# 3.net
KiCad netlist of a schematic drawn in EasyEDA Pro
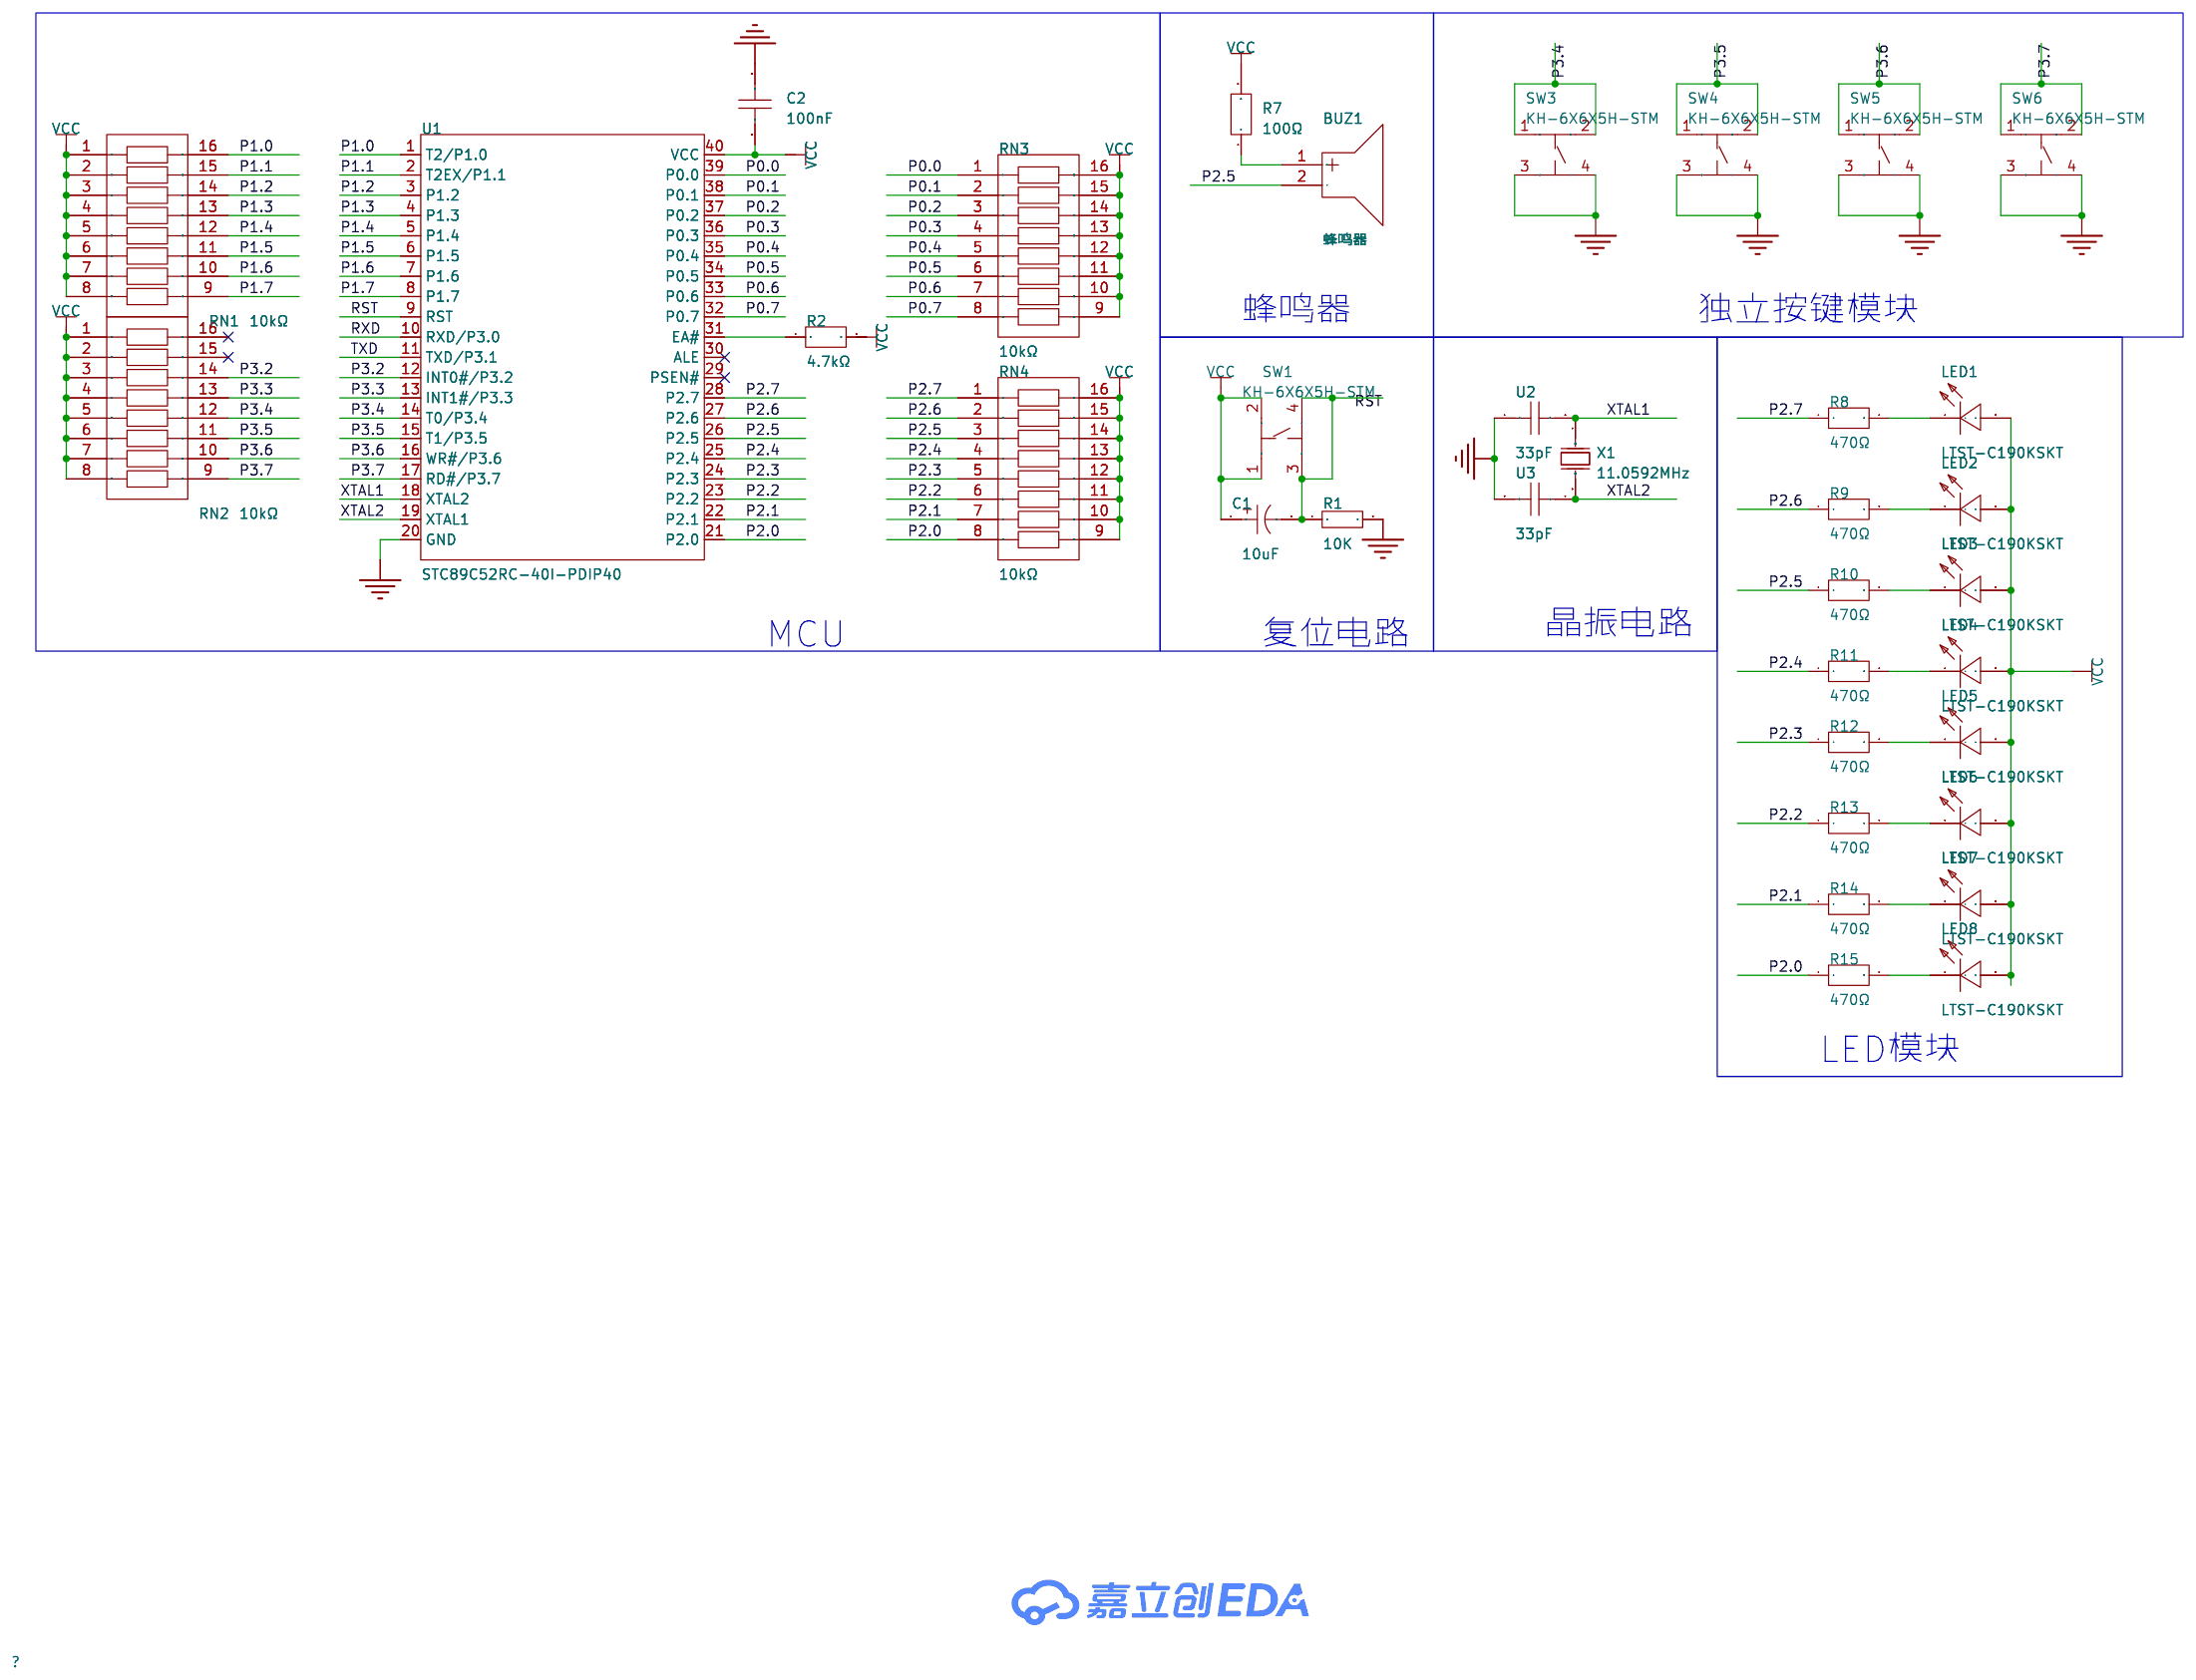
[diagram p0: schematic sheet]

(export (version "E")
  (design (tool "Eeschema 10.0.6"))
  (components
    (comp (ref "BUZ1")
      (value "蜂鸣器")
      (footprint "easyedapro:BUZ-TH_BD9.0-P5.00-D0.6-FD")
      (libsource (lib "easyedapro") (part "蜂鸣器"))
    )
    (comp (ref "C1")
      (value "10uF")
      (footprint "easyedapro:CAP-TH_BD10.0-P5.00-D0.6-FD_1")
      (description "容值:10uF;精度:±20%;额定电压:450V;纹波电流:200mA@100kHz;等效串联电阻(ESR):9Ω@100kHz;")
      (fields (field (name "Manufacturer Part") "CV100MPA16B") (field (name "Manufacturer") "TWBOR(伯鸿)"))
      (libsource (lib "easyedapro") (part "CV100MPA16B"))
    )
    (comp (ref "C2")
      (value "100nF")
      (footprint "easyedapro:C0603")
      (description "容值:100nF;精度:±10%;额定电压:25V;温度系数:X7R;")
      (fields
        (field (name "Manufacturer Part") "0603X7R104K250NT")
        (field (name "Manufacturer") "AIDE(爱迪电容)")
      )
      (libsource (lib "easyedapro") (part "0603X7R104K250NT"))
    )
    (comp (ref "LED1")
      (value "LTST-C190KSKT")
      (footprint "easyedapro:LED0603-RD")
      (fields (field (name "Manufacturer") "LITEON(光宝)"))
      (libsource (lib "easyedapro") (part "LTST-C190KSKT"))
    )
    (comp (ref "LED2")
      (value "LTST-C190KSKT")
      (footprint "easyedapro:LED0603-RD")
      (fields (field (name "Manufacturer") "LITEON(光宝)"))
      (libsource (lib "easyedapro") (part "LTST-C190KSKT"))
    )
    (comp (ref "LED3")
      (value "LTST-C190KSKT")
      (footprint "easyedapro:LED0603-RD")
      (fields (field (name "Manufacturer") "LITEON(光宝)"))
      (libsource (lib "easyedapro") (part "LTST-C190KSKT"))
    )
    (comp (ref "LED4")
      (value "LTST-C190KSKT")
      (footprint "easyedapro:LED0603-RD")
      (fields (field (name "Manufacturer") "LITEON(光宝)"))
      (libsource (lib "easyedapro") (part "LTST-C190KSKT"))
    )
    (comp (ref "LED5")
      (value "LTST-C190KSKT")
      (footprint "easyedapro:LED0603-RD")
      (fields (field (name "Manufacturer") "LITEON(光宝)"))
      (libsource (lib "easyedapro") (part "LTST-C190KSKT"))
    )
    (comp (ref "LED6")
      (value "LTST-C190KSKT")
      (footprint "easyedapro:LED0603-RD")
      (fields (field (name "Manufacturer") "LITEON(光宝)"))
      (libsource (lib "easyedapro") (part "LTST-C190KSKT"))
    )
    (comp (ref "LED7")
      (value "LTST-C190KSKT")
      (footprint "easyedapro:LED0603-RD")
      (fields (field (name "Manufacturer") "LITEON(光宝)"))
      (libsource (lib "easyedapro") (part "LTST-C190KSKT"))
    )
    (comp (ref "LED8")
      (value "LTST-C190KSKT")
      (footprint "easyedapro:LED0603-RD")
      (fields (field (name "Manufacturer") "LITEON(光宝)"))
      (libsource (lib "easyedapro") (part "LTST-C190KSKT"))
    )
    (comp (ref "R1") (value "10K") (footprint "easyedapro:R0603") (libsource (lib "easyedapro") (part "电阻")))
    (comp (ref "R2")
      (value "4.7kΩ")
      (footprint "easyedapro:R0805")
      (description "电阻类型:厚膜电阻;阻值:4.7kΩ;精度:±1%;功率:125mW;工作电压:-;温度系数:±100ppm/°C;")
      (fields
        (field (name "Manufacturer Part") "ERJ-U06F4701V")
        (field (name "Manufacturer") "PANASONIC(松下)")
      )
      (libsource (lib "easyedapro") (part "ERJ-U06F4701V"))
    )
    (comp (ref "R7")
      (value "100Ω")
      (footprint "easyedapro:R1206")
      (description "电阻类型:-;阻值:100Ω;精度:±5%;功率:250mW;工作电压:200V;")
      (fields
        (field (name "Manufacturer Part") "CQ06W4J0101T5E")
        (field (name "Manufacturer") "UNI-ROYAL(厚声)")
      )
      (libsource (lib "easyedapro") (part "CQ06W4J0101T5E"))
    )
    (comp (ref "R8")
      (value "470Ω")
      (footprint "easyedapro:R0402")
      (description "电阻类型:厚膜电阻;阻值:470Ω;精度:±1%;功率:62.5mW;工作电压:50V;温度系数:±100ppm/°C;")
      (fields (field (name "Manufacturer Part") "FRC0402F4700TS") (field (name "Manufacturer") "FOJAN(富捷)"))
      (libsource (lib "easyedapro") (part "FRC0402F4700TS"))
    )
    (comp (ref "R9")
      (value "470Ω")
      (footprint "easyedapro:R0402")
      (description "电阻类型:厚膜电阻;阻值:470Ω;精度:±1%;功率:62.5mW;工作电压:50V;温度系数:±100ppm/°C;")
      (fields (field (name "Manufacturer Part") "FRC0402F4700TS") (field (name "Manufacturer") "FOJAN(富捷)"))
      (libsource (lib "easyedapro") (part "FRC0402F4700TS"))
    )
    (comp (ref "R10")
      (value "470Ω")
      (footprint "easyedapro:R0402")
      (description "电阻类型:厚膜电阻;阻值:470Ω;精度:±1%;功率:62.5mW;工作电压:50V;温度系数:±100ppm/°C;")
      (fields (field (name "Manufacturer Part") "FRC0402F4700TS") (field (name "Manufacturer") "FOJAN(富捷)"))
      (libsource (lib "easyedapro") (part "FRC0402F4700TS"))
    )
    (comp (ref "R11")
      (value "470Ω")
      (footprint "easyedapro:R0402")
      (description "电阻类型:厚膜电阻;阻值:470Ω;精度:±1%;功率:62.5mW;工作电压:50V;温度系数:±100ppm/°C;")
      (fields (field (name "Manufacturer Part") "FRC0402F4700TS") (field (name "Manufacturer") "FOJAN(富捷)"))
      (libsource (lib "easyedapro") (part "FRC0402F4700TS"))
    )
    (comp (ref "R12")
      (value "470Ω")
      (footprint "easyedapro:R0402")
      (description "电阻类型:厚膜电阻;阻值:470Ω;精度:±1%;功率:62.5mW;工作电压:50V;温度系数:±100ppm/°C;")
      (fields (field (name "Manufacturer Part") "FRC0402F4700TS") (field (name "Manufacturer") "FOJAN(富捷)"))
      (libsource (lib "easyedapro") (part "FRC0402F4700TS"))
    )
    (comp (ref "R13")
      (value "470Ω")
      (footprint "easyedapro:R0402")
      (description "电阻类型:厚膜电阻;阻值:470Ω;精度:±1%;功率:62.5mW;工作电压:50V;温度系数:±100ppm/°C;")
      (fields (field (name "Manufacturer Part") "FRC0402F4700TS") (field (name "Manufacturer") "FOJAN(富捷)"))
      (libsource (lib "easyedapro") (part "FRC0402F4700TS"))
    )
    (comp (ref "R14")
      (value "470Ω")
      (footprint "easyedapro:R0402")
      (description "电阻类型:厚膜电阻;阻值:470Ω;精度:±1%;功率:62.5mW;工作电压:50V;温度系数:±100ppm/°C;")
      (fields (field (name "Manufacturer Part") "FRC0402F4700TS") (field (name "Manufacturer") "FOJAN(富捷)"))
      (libsource (lib "easyedapro") (part "FRC0402F4700TS"))
    )
    (comp (ref "R15")
      (value "470Ω")
      (footprint "easyedapro:R0402")
      (description "电阻类型:厚膜电阻;阻值:470Ω;精度:±1%;功率:62.5mW;工作电压:50V;温度系数:±100ppm/°C;")
      (fields (field (name "Manufacturer Part") "FRC0402F4700TS") (field (name "Manufacturer") "FOJAN(富捷)"))
      (libsource (lib "easyedapro") (part "FRC0402F4700TS"))
    )
    (comp (ref "RN1")
      (value "10kΩ")
      (footprint "easyedapro:DIP-16_L22.0-W6.7-P2.54-LS7.6-BL")
      (description "电阻器数:8;阻值:10kΩ;精度:±2%;单个元件功率:250mW;温度系数:±100ppm/°C;")
      (fields (field (name "Manufacturer Part") "4116R-1-103LF") (field (name "Manufacturer") "BOURNS"))
      (libsource (lib "easyedapro") (part "4116R-1-103LF"))
    )
    (comp (ref "RN2")
      (value "10kΩ")
      (footprint "easyedapro:DIP-16_L22.0-W6.7-P2.54-LS7.6-BL")
      (description "电阻器数:8;阻值:10kΩ;精度:±2%;单个元件功率:250mW;温度系数:±100ppm/°C;")
      (fields (field (name "Manufacturer Part") "4116R-1-103LF") (field (name "Manufacturer") "BOURNS"))
      (libsource (lib "easyedapro") (part "4116R-1-103LF"))
    )
    (comp (ref "RN3")
      (value "10kΩ")
      (footprint "easyedapro:DIP-16_L22.0-W6.7-P2.54-LS7.6-BL")
      (description "电阻器数:8;阻值:10kΩ;精度:±2%;单个元件功率:250mW;温度系数:±100ppm/°C;")
      (fields (field (name "Manufacturer Part") "4116R-1-103LF") (field (name "Manufacturer") "BOURNS"))
      (libsource (lib "easyedapro") (part "4116R-1-103LF"))
    )
    (comp (ref "RN4")
      (value "10kΩ")
      (footprint "easyedapro:DIP-16_L22.0-W6.7-P2.54-LS7.6-BL")
      (description "电阻器数:8;阻值:10kΩ;精度:±2%;单个元件功率:250mW;温度系数:±100ppm/°C;")
      (fields (field (name "Manufacturer Part") "4116R-1-103LF") (field (name "Manufacturer") "BOURNS"))
      (libsource (lib "easyedapro") (part "4116R-1-103LF"))
    )
    (comp (ref "SW1")
      (value "KH-6X6X5H-STM")
      (footprint "easyedapro:SW-SMD_4P-L6.0-W6.0-P4.50-LS9.0_H5.0")
      (description "电路结构:单刀单掷;按钮形状:圆形按钮;安装方式:立贴;开关长度:6mm;开关宽度:6mm;开关高度:5mm;带支架:不带;触点电流:50mA;额定电压(DC):12V;机械寿命:8万次;")
      (fields (field (name "Manufacturer") "kinghelm(金航标)"))
      (libsource (lib "easyedapro") (part "KH-6X6X5H-STM"))
    )
    (comp (ref "SW3")
      (value "KH-6X6X5H-STM")
      (footprint "easyedapro:SW-SMD_4P-L6.0-W6.0-P4.50-LS9.0_H5.0")
      (description "电路结构:单刀单掷;按钮形状:圆形按钮;安装方式:立贴;开关长度:6mm;开关宽度:6mm;开关高度:5mm;带支架:不带;触点电流:50mA;额定电压(DC):12V;机械寿命:8万次;")
      (fields (field (name "Manufacturer") "kinghelm(金航标)"))
      (libsource (lib "easyedapro") (part "KH-6X6X5H-STM"))
    )
    (comp (ref "SW4")
      (value "KH-6X6X5H-STM")
      (footprint "easyedapro:SW-SMD_4P-L6.0-W6.0-P4.50-LS9.0_H5.0")
      (description "电路结构:单刀单掷;按钮形状:圆形按钮;安装方式:立贴;开关长度:6mm;开关宽度:6mm;开关高度:5mm;带支架:不带;触点电流:50mA;额定电压(DC):12V;机械寿命:8万次;")
      (fields (field (name "Manufacturer") "kinghelm(金航标)"))
      (libsource (lib "easyedapro") (part "KH-6X6X5H-STM"))
    )
    (comp (ref "SW5")
      (value "KH-6X6X5H-STM")
      (footprint "easyedapro:SW-SMD_4P-L6.0-W6.0-P4.50-LS9.0_H5.0")
      (description "电路结构:单刀单掷;按钮形状:圆形按钮;安装方式:立贴;开关长度:6mm;开关宽度:6mm;开关高度:5mm;带支架:不带;触点电流:50mA;额定电压(DC):12V;机械寿命:8万次;")
      (fields (field (name "Manufacturer") "kinghelm(金航标)"))
      (libsource (lib "easyedapro") (part "KH-6X6X5H-STM"))
    )
    (comp (ref "SW6")
      (value "KH-6X6X5H-STM")
      (footprint "easyedapro:SW-SMD_4P-L6.0-W6.0-P4.50-LS9.0_H5.0")
      (description "电路结构:单刀单掷;按钮形状:圆形按钮;安装方式:立贴;开关长度:6mm;开关宽度:6mm;开关高度:5mm;带支架:不带;触点电流:50mA;额定电压(DC):12V;机械寿命:8万次;")
      (fields (field (name "Manufacturer") "kinghelm(金航标)"))
      (libsource (lib "easyedapro") (part "KH-6X6X5H-STM"))
    )
    (comp (ref "U1")
      (value "STC89C52RC-40I-PDIP40")
      (footprint "easyedapro:DIP-40_L52.0-W13.7-P2.54-LS15.2-BL")
      (description "CPU内核:51系列;应用领域:-;")
      (fields (field (name "Manufacturer") "STC"))
      (libsource (lib "easyedapro") (part "STC89C52RC-40I"))
    )
    (comp (ref "U2")
      (value "33pF")
      (footprint "easyedapro:C0603")
      (description "容值:33pF;精度:±1%;额定电压:50V;温度系数:-;")
      (fields
        (field (name "Manufacturer Part") "GRM1885C1H330FA01D")
        (field (name "Manufacturer") "muRata(村田)")
      )
      (libsource (lib "easyedapro") (part "GRM1885C1H330FA01D"))
    )
    (comp (ref "U3")
      (value "33pF")
      (footprint "easyedapro:C0603")
      (description "容值:33pF;精度:±1%;额定电压:50V;温度系数:-;")
      (fields
        (field (name "Manufacturer Part") "GRM1885C1H330FA01D")
        (field (name "Manufacturer") "muRata(村田)")
      )
      (libsource (lib "easyedapro") (part "GRM1885C1H330FA01D"))
    )
    (comp (ref "X1")
      (value "11.0592MHz")
      (footprint "easyedapro:HC-49US_L11.5-W4.5-P4.88")
      (description "晶振类型:直插晶振;频率:11.0592MHz;常温频差:±20ppm;负载电容:20pF;频率稳定度:±30ppm;")
      (fields
        (field (name "Manufacturer Part") "X49SD110592MSD2SC")
        (field (name "Manufacturer") "YXC(扬兴晶振)")
      )
      (libsource (lib "easyedapro") (part "X49SD110592MSD2SC"))
    )
  )
  (nets
    (net (code "1") (name "/P0.0") (class "Default")
      (node (ref "RN3") (pin "1") (pinfunction "1_1") (pintype "unspecified"))
      (node (ref "U1") (pin "39") (pinfunction "P0.0_39") (pintype "unspecified"))
    )
    (net (code "2") (name "/P0.1") (class "Default")
      (node (ref "RN3") (pin "2") (pinfunction "2_2") (pintype "unspecified"))
      (node (ref "U1") (pin "38") (pinfunction "P0.1_38") (pintype "unspecified"))
    )
    (net (code "3") (name "/P0.2") (class "Default")
      (node (ref "RN3") (pin "3") (pinfunction "3_3") (pintype "unspecified"))
      (node (ref "U1") (pin "37") (pinfunction "P0.2_37") (pintype "unspecified"))
    )
    (net (code "4") (name "/P0.3") (class "Default")
      (node (ref "RN3") (pin "4") (pinfunction "4_4") (pintype "unspecified"))
      (node (ref "U1") (pin "36") (pinfunction "P0.3_36") (pintype "unspecified"))
    )
    (net (code "5") (name "/P0.4") (class "Default")
      (node (ref "RN3") (pin "5") (pinfunction "5_5") (pintype "unspecified"))
      (node (ref "U1") (pin "35") (pinfunction "P0.4_35") (pintype "unspecified"))
    )
    (net (code "6") (name "/P0.5") (class "Default")
      (node (ref "RN3") (pin "6") (pinfunction "6_6") (pintype "unspecified"))
      (node (ref "U1") (pin "34") (pinfunction "P0.5_34") (pintype "unspecified"))
    )
    (net (code "7") (name "/P0.6") (class "Default")
      (node (ref "RN3") (pin "7") (pinfunction "7_7") (pintype "unspecified"))
      (node (ref "U1") (pin "33") (pinfunction "P0.6_33") (pintype "unspecified"))
    )
    (net (code "8") (name "/P0.7") (class "Default")
      (node (ref "RN3") (pin "8") (pinfunction "8_8") (pintype "unspecified"))
      (node (ref "U1") (pin "32") (pinfunction "P0.7_32") (pintype "unspecified"))
    )
    (net (code "9") (name "/P1.0") (class "Default")
      (node (ref "RN1") (pin "16") (pinfunction "16_16") (pintype "unspecified"))
      (node (ref "U1") (pin "1") (pinfunction "T2/P1.0_1") (pintype "unspecified"))
    )
    (net (code "10") (name "/P1.1") (class "Default")
      (node (ref "RN1") (pin "15") (pinfunction "15_15") (pintype "unspecified"))
      (node (ref "U1") (pin "2") (pinfunction "T2EX/P1.1_2") (pintype "unspecified"))
    )
    (net (code "11") (name "/P1.2") (class "Default")
      (node (ref "RN1") (pin "14") (pinfunction "14_14") (pintype "unspecified"))
      (node (ref "U1") (pin "3") (pinfunction "P1.2_3") (pintype "unspecified"))
    )
    (net (code "12") (name "/P1.3") (class "Default")
      (node (ref "RN1") (pin "13") (pinfunction "13_13") (pintype "unspecified"))
      (node (ref "U1") (pin "4") (pinfunction "P1.3_4") (pintype "unspecified"))
    )
    (net (code "13") (name "/P1.4") (class "Default")
      (node (ref "RN1") (pin "12") (pinfunction "12_12") (pintype "unspecified"))
      (node (ref "U1") (pin "5") (pinfunction "P1.4_5") (pintype "unspecified"))
    )
    (net (code "14") (name "/P1.5") (class "Default")
      (node (ref "RN1") (pin "11") (pinfunction "11_11") (pintype "unspecified"))
      (node (ref "U1") (pin "6") (pinfunction "P1.5_6") (pintype "unspecified"))
    )
    (net (code "15") (name "/P1.6") (class "Default")
      (node (ref "RN1") (pin "10") (pinfunction "10_10") (pintype "unspecified"))
      (node (ref "U1") (pin "7") (pinfunction "P1.6_7") (pintype "unspecified"))
    )
    (net (code "16") (name "/P1.7") (class "Default")
      (node (ref "RN1") (pin "9") (pinfunction "9_9") (pintype "unspecified"))
      (node (ref "U1") (pin "8") (pinfunction "P1.7_8") (pintype "unspecified"))
    )
    (net (code "17") (name "/P2.0") (class "Default")
      (node (ref "R15") (pin "1") (pinfunction "1_1") (pintype "unspecified"))
      (node (ref "RN4") (pin "8") (pinfunction "8_8") (pintype "unspecified"))
      (node (ref "U1") (pin "21") (pinfunction "P2.0_21") (pintype "unspecified"))
    )
    (net (code "18") (name "/P2.1") (class "Default")
      (node (ref "R14") (pin "1") (pinfunction "1_1") (pintype "unspecified"))
      (node (ref "RN4") (pin "7") (pinfunction "7_7") (pintype "unspecified"))
      (node (ref "U1") (pin "22") (pinfunction "P2.1_22") (pintype "unspecified"))
    )
    (net (code "19") (name "/P2.2") (class "Default")
      (node (ref "R13") (pin "1") (pinfunction "1_1") (pintype "unspecified"))
      (node (ref "RN4") (pin "6") (pinfunction "6_6") (pintype "unspecified"))
      (node (ref "U1") (pin "23") (pinfunction "P2.2_23") (pintype "unspecified"))
    )
    (net (code "20") (name "/P2.3") (class "Default")
      (node (ref "R12") (pin "1") (pinfunction "1_1") (pintype "unspecified"))
      (node (ref "RN4") (pin "5") (pinfunction "5_5") (pintype "unspecified"))
      (node (ref "U1") (pin "24") (pinfunction "P2.3_24") (pintype "unspecified"))
    )
    (net (code "21") (name "/P2.4") (class "Default")
      (node (ref "R11") (pin "1") (pinfunction "1_1") (pintype "unspecified"))
      (node (ref "RN4") (pin "4") (pinfunction "4_4") (pintype "unspecified"))
      (node (ref "U1") (pin "25") (pinfunction "P2.4_25") (pintype "unspecified"))
    )
    (net (code "22") (name "/P2.5") (class "Default")
      (node (ref "BUZ1") (pin "2") (pinfunction "-_2") (pintype "unspecified"))
      (node (ref "R10") (pin "1") (pinfunction "1_1") (pintype "unspecified"))
      (node (ref "RN4") (pin "3") (pinfunction "3_3") (pintype "unspecified"))
      (node (ref "U1") (pin "26") (pinfunction "P2.5_26") (pintype "unspecified"))
    )
    (net (code "23") (name "/P2.6") (class "Default")
      (node (ref "R9") (pin "1") (pinfunction "1_1") (pintype "unspecified"))
      (node (ref "RN4") (pin "2") (pinfunction "2_2") (pintype "unspecified"))
      (node (ref "U1") (pin "27") (pinfunction "P2.6_27") (pintype "unspecified"))
    )
    (net (code "24") (name "/P2.7") (class "Default")
      (node (ref "R8") (pin "1") (pinfunction "1_1") (pintype "unspecified"))
      (node (ref "RN4") (pin "1") (pinfunction "1_1") (pintype "unspecified"))
      (node (ref "U1") (pin "28") (pinfunction "P2.7_28") (pintype "unspecified"))
    )
    (net (code "25") (name "/P3.2") (class "Default")
      (node (ref "RN2") (pin "14") (pinfunction "14_14") (pintype "unspecified"))
      (node (ref "U1") (pin "12") (pinfunction "INT0#/P3.2_12") (pintype "unspecified"))
    )
    (net (code "26") (name "/P3.3") (class "Default")
      (node (ref "RN2") (pin "13") (pinfunction "13_13") (pintype "unspecified"))
      (node (ref "U1") (pin "13") (pinfunction "INT1#/P3.3_13") (pintype "unspecified"))
    )
    (net (code "27") (name "/P3.4") (class "Default")
      (node (ref "RN2") (pin "12") (pinfunction "12_12") (pintype "unspecified"))
      (node (ref "SW3") (pin "1") (pinfunction "1_1") (pintype "unspecified"))
      (node (ref "SW3") (pin "2") (pinfunction "2_2") (pintype "unspecified"))
      (node (ref "U1") (pin "14") (pinfunction "T0/P3.4_14") (pintype "unspecified"))
    )
    (net (code "28") (name "/P3.5") (class "Default")
      (node (ref "RN2") (pin "11") (pinfunction "11_11") (pintype "unspecified"))
      (node (ref "SW4") (pin "1") (pinfunction "1_1") (pintype "unspecified"))
      (node (ref "SW4") (pin "2") (pinfunction "2_2") (pintype "unspecified"))
      (node (ref "U1") (pin "15") (pinfunction "T1/P3.5_15") (pintype "unspecified"))
    )
    (net (code "29") (name "/P3.6") (class "Default")
      (node (ref "RN2") (pin "10") (pinfunction "10_10") (pintype "unspecified"))
      (node (ref "SW5") (pin "1") (pinfunction "1_1") (pintype "unspecified"))
      (node (ref "SW5") (pin "2") (pinfunction "2_2") (pintype "unspecified"))
      (node (ref "U1") (pin "16") (pinfunction "WR#/P3.6_16") (pintype "unspecified"))
    )
    (net (code "30") (name "/P3.7") (class "Default")
      (node (ref "RN2") (pin "9") (pinfunction "9_9") (pintype "unspecified"))
      (node (ref "SW6") (pin "1") (pinfunction "1_1") (pintype "unspecified"))
      (node (ref "SW6") (pin "2") (pinfunction "2_2") (pintype "unspecified"))
      (node (ref "U1") (pin "17") (pinfunction "RD#/P3.7_17") (pintype "unspecified"))
    )
    (net (code "31") (name "/RST") (class "Default")
      (node (ref "C1") (pin "2") (pinfunction "2_2") (pintype "input"))
      (node (ref "R1") (pin "1") (pinfunction "1_1") (pintype "input"))
      (node (ref "SW1") (pin "3") (pinfunction "3_3") (pintype "unspecified"))
      (node (ref "SW1") (pin "4") (pinfunction "4_4") (pintype "unspecified"))
      (node (ref "U1") (pin "9") (pinfunction "RST_9") (pintype "unspecified"))
    )
    (net (code "32") (name "/RXD") (class "Default")
      (node (ref "U1") (pin "10") (pinfunction "RXD/P3.0_10") (pintype "unspecified"))
    )
    (net (code "33") (name "/TXD") (class "Default")
      (node (ref "U1") (pin "11") (pinfunction "TXD/P3.1_11") (pintype "unspecified"))
    )
    (net (code "34") (name "/XTAL1") (class "Default")
      (node (ref "U1") (pin "18") (pinfunction "XTAL2_18") (pintype "unspecified"))
      (node (ref "U2") (pin "2") (pinfunction "2_2") (pintype "unspecified"))
      (node (ref "X1") (pin "1") (pinfunction "OSC1_1") (pintype "input"))
    )
    (net (code "35") (name "/XTAL2") (class "Default")
      (node (ref "U1") (pin "19") (pinfunction "XTAL1_19") (pintype "unspecified"))
      (node (ref "U3") (pin "1") (pinfunction "1_1") (pintype "unspecified"))
      (node (ref "X1") (pin "2") (pinfunction "OSC2_2") (pintype "input"))
    )
    (net (code "36") (name "GND") (class "Default")
      (node (ref "C2") (pin "2") (pinfunction "2_2") (pintype "unspecified"))
      (node (ref "R1") (pin "2") (pinfunction "2_2") (pintype "input"))
      (node (ref "SW3") (pin "3") (pinfunction "3_3") (pintype "unspecified"))
      (node (ref "SW3") (pin "4") (pinfunction "4_4") (pintype "unspecified"))
      (node (ref "SW4") (pin "3") (pinfunction "3_3") (pintype "unspecified"))
      (node (ref "SW4") (pin "4") (pinfunction "4_4") (pintype "unspecified"))
      (node (ref "SW5") (pin "3") (pinfunction "3_3") (pintype "unspecified"))
      (node (ref "SW5") (pin "4") (pinfunction "4_4") (pintype "unspecified"))
      (node (ref "SW6") (pin "3") (pinfunction "3_3") (pintype "unspecified"))
      (node (ref "SW6") (pin "4") (pinfunction "4_4") (pintype "unspecified"))
      (node (ref "U1") (pin "20") (pinfunction "GND_20") (pintype "unspecified"))
      (node (ref "U2") (pin "1") (pinfunction "1_1") (pintype "unspecified"))
      (node (ref "U3") (pin "2") (pinfunction "2_2") (pintype "unspecified"))
    )
    (net (code "37") (name "Net-(BUZ1-+)") (class "Default")
      (node (ref "BUZ1") (pin "1") (pinfunction "+_1") (pintype "unspecified"))
      (node (ref "R7") (pin "1") (pinfunction "1_1") (pintype "unspecified"))
    )
    (net (code "38") (name "Net-(LED1--)") (class "Default")
      (node (ref "LED1") (pin "1") (pinfunction "-_1") (pintype "unspecified"))
      (node (ref "R8") (pin "2") (pinfunction "2_2") (pintype "unspecified"))
    )
    (net (code "39") (name "Net-(LED2--)") (class "Default")
      (node (ref "LED2") (pin "1") (pinfunction "-_1") (pintype "unspecified"))
      (node (ref "R9") (pin "2") (pinfunction "2_2") (pintype "unspecified"))
    )
    (net (code "40") (name "Net-(LED3--)") (class "Default")
      (node (ref "LED3") (pin "1") (pinfunction "-_1") (pintype "unspecified"))
      (node (ref "R10") (pin "2") (pinfunction "2_2") (pintype "unspecified"))
    )
    (net (code "41") (name "Net-(LED4--)") (class "Default")
      (node (ref "LED4") (pin "1") (pinfunction "-_1") (pintype "unspecified"))
      (node (ref "R11") (pin "2") (pinfunction "2_2") (pintype "unspecified"))
    )
    (net (code "42") (name "Net-(LED5--)") (class "Default")
      (node (ref "LED5") (pin "1") (pinfunction "-_1") (pintype "unspecified"))
      (node (ref "R12") (pin "2") (pinfunction "2_2") (pintype "unspecified"))
    )
    (net (code "43") (name "Net-(LED6--)") (class "Default")
      (node (ref "LED6") (pin "1") (pinfunction "-_1") (pintype "unspecified"))
      (node (ref "R13") (pin "2") (pinfunction "2_2") (pintype "unspecified"))
    )
    (net (code "44") (name "Net-(LED7--)") (class "Default")
      (node (ref "LED7") (pin "1") (pinfunction "-_1") (pintype "unspecified"))
      (node (ref "R14") (pin "2") (pinfunction "2_2") (pintype "unspecified"))
    )
    (net (code "45") (name "Net-(LED8--)") (class "Default")
      (node (ref "LED8") (pin "1") (pinfunction "-_1") (pintype "unspecified"))
      (node (ref "R15") (pin "2") (pinfunction "2_2") (pintype "unspecified"))
    )
    (net (code "46") (name "Net-(U1-EA#)") (class "Default")
      (node (ref "R2") (pin "1") (pinfunction "1_1") (pintype "unspecified"))
      (node (ref "U1") (pin "31") (pinfunction "EA#_31") (pintype "unspecified"))
    )
    (net (code "47") (name "VCC") (class "Default")
      (node (ref "C1") (pin "1") (pinfunction "1_1") (pintype "input"))
      (node (ref "C2") (pin "1") (pinfunction "1_1") (pintype "unspecified"))
      (node (ref "LED1") (pin "2") (pinfunction "+_2") (pintype "unspecified"))
      (node (ref "LED2") (pin "2") (pinfunction "+_2") (pintype "unspecified"))
      (node (ref "LED3") (pin "2") (pinfunction "+_2") (pintype "unspecified"))
      (node (ref "LED4") (pin "2") (pinfunction "+_2") (pintype "unspecified"))
      (node (ref "LED5") (pin "2") (pinfunction "+_2") (pintype "unspecified"))
      (node (ref "LED6") (pin "2") (pinfunction "+_2") (pintype "unspecified"))
      (node (ref "LED7") (pin "2") (pinfunction "+_2") (pintype "unspecified"))
      (node (ref "LED8") (pin "2") (pinfunction "+_2") (pintype "unspecified"))
      (node (ref "R2") (pin "2") (pinfunction "2_2") (pintype "unspecified"))
      (node (ref "R7") (pin "2") (pinfunction "2_2") (pintype "unspecified"))
      (node (ref "RN1") (pin "1") (pinfunction "1_1") (pintype "unspecified"))
      (node (ref "RN1") (pin "2") (pinfunction "2_2") (pintype "unspecified"))
      (node (ref "RN1") (pin "3") (pinfunction "3_3") (pintype "unspecified"))
      (node (ref "RN1") (pin "4") (pinfunction "4_4") (pintype "unspecified"))
      (node (ref "RN1") (pin "5") (pinfunction "5_5") (pintype "unspecified"))
      (node (ref "RN1") (pin "6") (pinfunction "6_6") (pintype "unspecified"))
      (node (ref "RN1") (pin "7") (pinfunction "7_7") (pintype "unspecified"))
      (node (ref "RN1") (pin "8") (pinfunction "8_8") (pintype "unspecified"))
      (node (ref "RN2") (pin "1") (pinfunction "1_1") (pintype "unspecified"))
      (node (ref "RN2") (pin "2") (pinfunction "2_2") (pintype "unspecified"))
      (node (ref "RN2") (pin "3") (pinfunction "3_3") (pintype "unspecified"))
      (node (ref "RN2") (pin "4") (pinfunction "4_4") (pintype "unspecified"))
      (node (ref "RN2") (pin "5") (pinfunction "5_5") (pintype "unspecified"))
      (node (ref "RN2") (pin "6") (pinfunction "6_6") (pintype "unspecified"))
      (node (ref "RN2") (pin "7") (pinfunction "7_7") (pintype "unspecified"))
      (node (ref "RN2") (pin "8") (pinfunction "8_8") (pintype "unspecified"))
      (node (ref "RN3") (pin "10") (pinfunction "10_10") (pintype "unspecified"))
      (node (ref "RN3") (pin "11") (pinfunction "11_11") (pintype "unspecified"))
      (node (ref "RN3") (pin "12") (pinfunction "12_12") (pintype "unspecified"))
      (node (ref "RN3") (pin "13") (pinfunction "13_13") (pintype "unspecified"))
      (node (ref "RN3") (pin "14") (pinfunction "14_14") (pintype "unspecified"))
      (node (ref "RN3") (pin "15") (pinfunction "15_15") (pintype "unspecified"))
      (node (ref "RN3") (pin "16") (pinfunction "16_16") (pintype "unspecified"))
      (node (ref "RN3") (pin "9") (pinfunction "9_9") (pintype "unspecified"))
      (node (ref "RN4") (pin "10") (pinfunction "10_10") (pintype "unspecified"))
      (node (ref "RN4") (pin "11") (pinfunction "11_11") (pintype "unspecified"))
      (node (ref "RN4") (pin "12") (pinfunction "12_12") (pintype "unspecified"))
      (node (ref "RN4") (pin "13") (pinfunction "13_13") (pintype "unspecified"))
      (node (ref "RN4") (pin "14") (pinfunction "14_14") (pintype "unspecified"))
      (node (ref "RN4") (pin "15") (pinfunction "15_15") (pintype "unspecified"))
      (node (ref "RN4") (pin "16") (pinfunction "16_16") (pintype "unspecified"))
      (node (ref "RN4") (pin "9") (pinfunction "9_9") (pintype "unspecified"))
      (node (ref "SW1") (pin "1") (pinfunction "1_1") (pintype "unspecified"))
      (node (ref "SW1") (pin "2") (pinfunction "2_2") (pintype "unspecified"))
      (node (ref "U1") (pin "40") (pinfunction "VCC_40") (pintype "unspecified"))
    )
    (net (code "48") (name "unconnected-(RN2-Pad15)") (class "Default")
      (node (ref "RN2") (pin "15") (pinfunction "15_15") (pintype "unspecified+no_connect"))
    )
    (net (code "49") (name "unconnected-(RN2-Pad16)") (class "Default")
      (node (ref "RN2") (pin "16") (pinfunction "16_16") (pintype "unspecified+no_connect"))
    )
    (net (code "50") (name "unconnected-(U1-ALE-Pad30)") (class "Default")
      (node (ref "U1") (pin "30") (pinfunction "ALE_30") (pintype "unspecified+no_connect"))
    )
    (net (code "51") (name "unconnected-(U1-PSEN#-Pad29)") (class "Default")
      (node (ref "U1") (pin "29") (pinfunction "PSEN#_29") (pintype "unspecified+no_connect"))
    )
  )
)
